# fan-faker.net
KiCad netlist of a schematic drawn in EAGLE
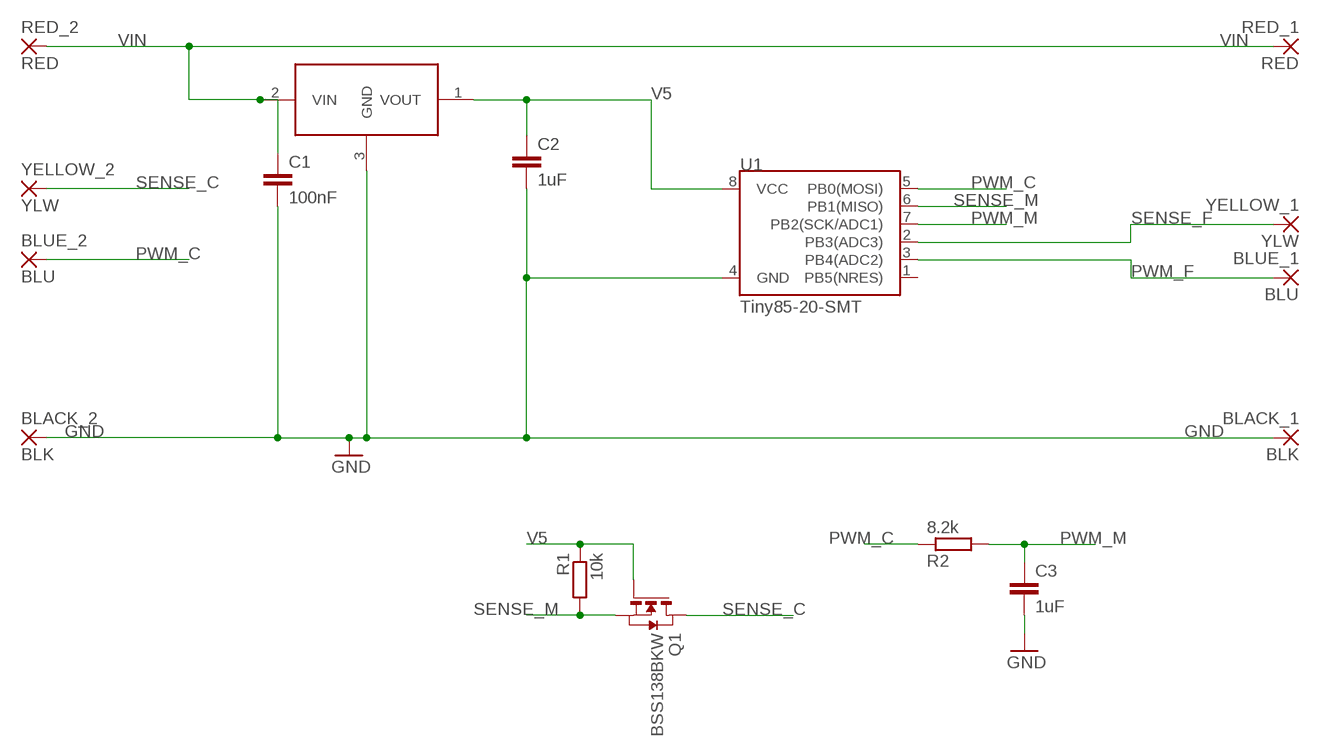
[diagram p0: schematic, sheet 1]

(export (version "E")
  (design (tool "Eeschema 10.0.6"))
  (components
    (comp (ref "BLACK_1")
      (value "BLK")
      (footprint "eagle-import:2,54_1,0")
      (libsource (lib "eagle-import") (part "2,54/1,0"))
    )
    (comp (ref "BLACK_2")
      (value "BLK")
      (footprint "eagle-import:2,54_1,0")
      (libsource (lib "eagle-import") (part "2,54/1,0"))
    )
    (comp (ref "BLUE_1")
      (value "BLU")
      (footprint "eagle-import:2,54_1,0")
      (libsource (lib "eagle-import") (part "2,54/1,0"))
    )
    (comp (ref "BLUE_2")
      (value "BLU")
      (footprint "eagle-import:2,54_1,0")
      (libsource (lib "eagle-import") (part "2,54/1,0"))
    )
    (comp (ref "C1")
      (value "100nF")
      (footprint "eagle-import:C0805K")
      (libsource (lib "eagle-import") (part "C-EUC0805K"))
    )
    (comp (ref "C2")
      (value "1uF")
      (footprint "eagle-import:C0805K")
      (libsource (lib "eagle-import") (part "C-EUC0805K"))
    )
    (comp (ref "C3")
      (value "1uF")
      (footprint "eagle-import:C0805K")
      (libsource (lib "eagle-import") (part "C-EUC0805K"))
    )
    (comp (ref "Q1")
      (value "BSS138BKW")
      (footprint "eagle-import:SOT323")
      (libsource (lib "eagle-import") (part "BSS138BKW"))
    )
    (comp (ref "R1")
      (value "10k")
      (footprint "eagle-import:R0805")
      (libsource (lib "eagle-import") (part "R-EU_R0805"))
    )
    (comp (ref "R2")
      (value "8.2k")
      (footprint "eagle-import:R0805")
      (libsource (lib "eagle-import") (part "R-EU_R0805"))
    )
    (comp (ref "RED_1")
      (value "RED")
      (footprint "eagle-import:2,54_1,0")
      (libsource (lib "eagle-import") (part "2,54/1,0"))
    )
    (comp (ref "RED_2")
      (value "RED")
      (footprint "eagle-import:2,54_1,0")
      (libsource (lib "eagle-import") (part "2,54/1,0"))
    )
    (comp (ref "U$2")
      (value "LM3480")
      (footprint "eagle-import:SOT23")
      (libsource (lib "eagle-import") (part "LM3480"))
    )
    (comp (ref "U1")
      (value "Tiny85-20-SMT")
      (footprint "eagle-import:SO08-EIAJ")
      (libsource (lib "eagle-import") (part "ATTINY45TINY85-20-SMT"))
    )
    (comp (ref "YELLOW_1")
      (value "YLW")
      (footprint "eagle-import:2,54_1,0")
      (libsource (lib "eagle-import") (part "2,54/1,0"))
    )
    (comp (ref "YELLOW_2")
      (value "YLW")
      (footprint "eagle-import:2,54_1,0")
      (libsource (lib "eagle-import") (part "2,54/1,0"))
    )
  )
  (nets
    (net (code "1") (name "/PWM_C") (class "Default")
      (node (ref "BLUE_2") (pin "1") (pinfunction "P_1") (pintype "passive"))
      (node (ref "R2") (pin "1") (pinfunction "1_1") (pintype "passive"))
      (node (ref "U1") (pin "5") (pinfunction "PB0(MOSI)_5") (pintype "bidirectional"))
    )
    (net (code "2") (name "/PWM_F") (class "Default")
      (node (ref "BLUE_1") (pin "1") (pinfunction "P_1") (pintype "passive"))
      (node (ref "U1") (pin "3") (pinfunction "PB4(ADC2)_3") (pintype "bidirectional"))
    )
    (net (code "3") (name "/PWM_M") (class "Default")
      (node (ref "C3") (pin "1") (pinfunction "1_1") (pintype "passive"))
      (node (ref "R2") (pin "2") (pinfunction "2_2") (pintype "passive"))
      (node (ref "U1") (pin "7") (pinfunction "PB2(SCK/ADC1)_7") (pintype "bidirectional"))
    )
    (net (code "4") (name "/SENSE_C") (class "Default")
      (node (ref "Q1") (pin "1") (pinfunction "D_1") (pintype "passive"))
      (node (ref "YELLOW_2") (pin "1") (pinfunction "P_1") (pintype "passive"))
    )
    (net (code "5") (name "/SENSE_F") (class "Default")
      (node (ref "U1") (pin "2") (pinfunction "PB3(ADC3)_2") (pintype "bidirectional"))
      (node (ref "YELLOW_1") (pin "1") (pinfunction "P_1") (pintype "passive"))
    )
    (net (code "6") (name "/SENSE_M") (class "Default")
      (node (ref "Q1") (pin "3") (pinfunction "S_3") (pintype "passive"))
      (node (ref "R1") (pin "2") (pinfunction "2_2") (pintype "passive"))
      (node (ref "U1") (pin "6") (pinfunction "PB1(MISO)_6") (pintype "bidirectional"))
    )
    (net (code "7") (name "/V5") (class "Default")
      (node (ref "C2") (pin "1") (pinfunction "1_1") (pintype "passive"))
      (node (ref "Q1") (pin "2") (pinfunction "G_2") (pintype "passive"))
      (node (ref "R1") (pin "1") (pinfunction "1_1") (pintype "passive"))
      (node (ref "U$2") (pin "1") (pinfunction "VOUT_1") (pintype "passive"))
      (node (ref "U1") (pin "8") (pinfunction "VCC_8") (pintype "bidirectional"))
    )
    (net (code "8") (name "/VIN") (class "Default")
      (node (ref "C1") (pin "1") (pinfunction "1_1") (pintype "passive"))
      (node (ref "RED_1") (pin "1") (pinfunction "P_1") (pintype "passive"))
      (node (ref "RED_2") (pin "1") (pinfunction "P_1") (pintype "passive"))
      (node (ref "U$2") (pin "2") (pinfunction "VIN_2") (pintype "passive"))
    )
    (net (code "9") (name "GND") (class "Default")
      (node (ref "BLACK_1") (pin "1") (pinfunction "P_1") (pintype "passive"))
      (node (ref "BLACK_2") (pin "1") (pinfunction "P_1") (pintype "passive"))
      (node (ref "C1") (pin "2") (pinfunction "2_2") (pintype "passive"))
      (node (ref "C2") (pin "2") (pinfunction "2_2") (pintype "passive"))
      (node (ref "C3") (pin "2") (pinfunction "2_2") (pintype "passive"))
      (node (ref "U$2") (pin "3") (pinfunction "GND_3") (pintype "passive"))
      (node (ref "U1") (pin "4") (pinfunction "GND_4") (pintype "bidirectional"))
    )
    (net (code "10") (name "unconnected-(U1-PB5(NRES)-Pad1)") (class "Default")
      (node (ref "U1") (pin "1") (pinfunction "PB5(NRES)_1") (pintype "bidirectional"))
    )
  )
)
